# HydraBus_1_0_Rev1_3.net
KiCad netlist of a schematic drawn in EAGLE
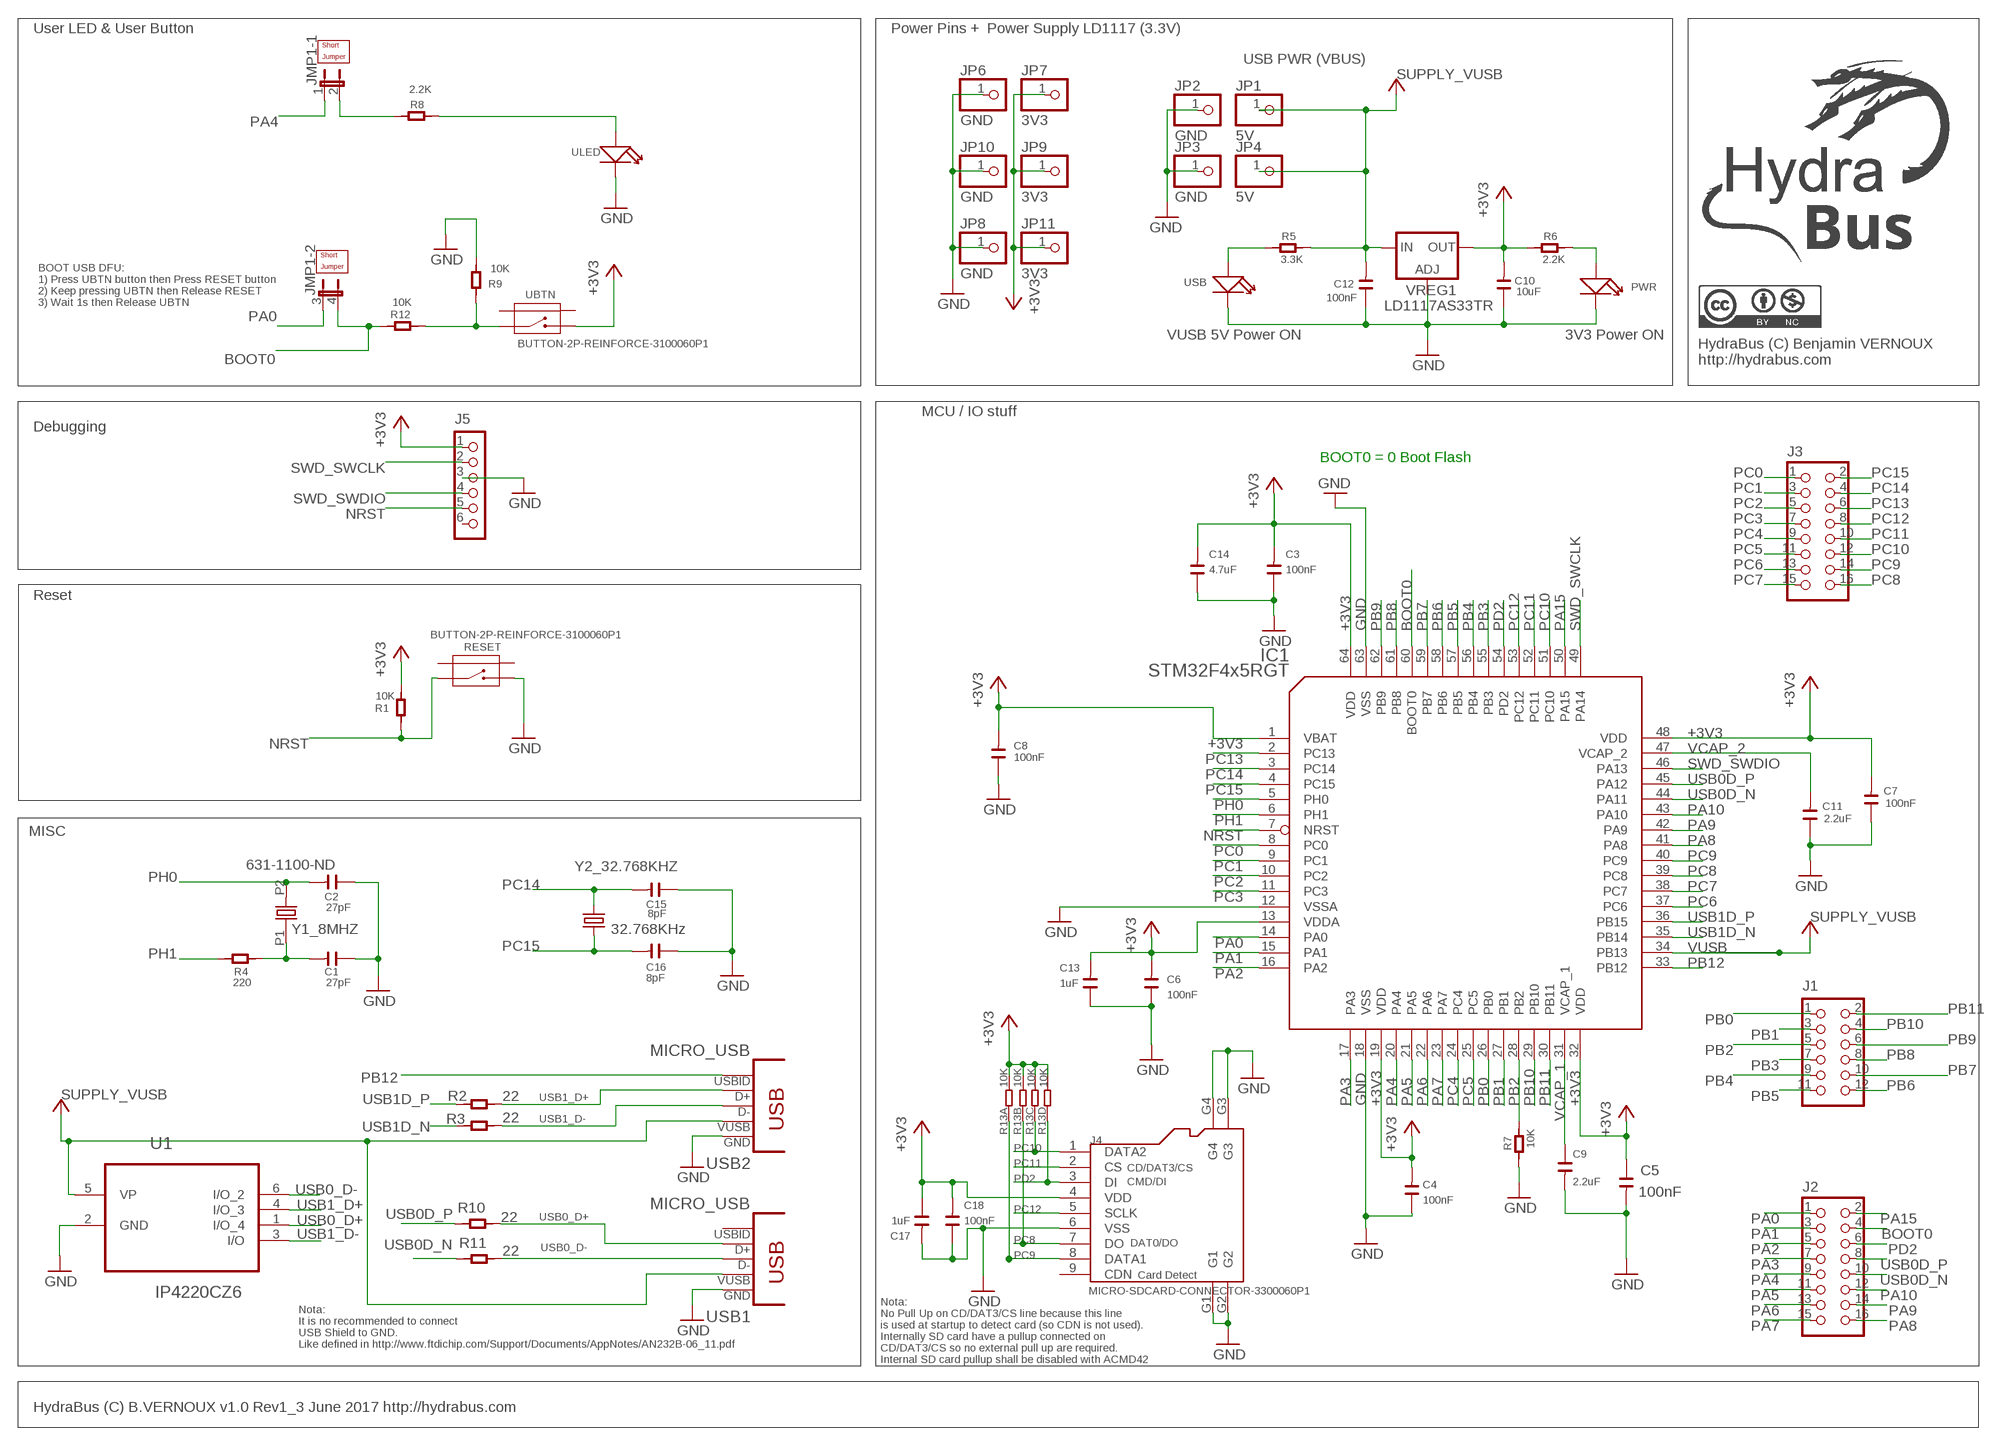
[diagram p0: schematic, sheet 1]

(export (version "E")
  (design (tool "Eeschema 10.0.6"))
  (components
    (comp (ref "C1")
      (value "27pF")
      (footprint "eagle-import:C0603")
      (libsource (lib "eagle-import") (part "C-0603"))
    )
    (comp (ref "C2")
      (value "27pF")
      (footprint "eagle-import:C0603")
      (libsource (lib "eagle-import") (part "C-0603"))
    )
    (comp (ref "C3")
      (value "100nF")
      (footprint "eagle-import:C0603")
      (libsource (lib "eagle-import") (part "C-0603"))
    )
    (comp (ref "C4")
      (value "100nF")
      (footprint "eagle-import:C0603")
      (libsource (lib "eagle-import") (part "C-0603"))
    )
    (comp (ref "C5")
      (value "100nF")
      (footprint "eagle-import:C0603")
      (libsource (lib "eagle-import") (part "C-0603"))
    )
    (comp (ref "C6")
      (value "100nF")
      (footprint "eagle-import:C0603")
      (libsource (lib "eagle-import") (part "C-0603"))
    )
    (comp (ref "C7")
      (value "100nF")
      (footprint "eagle-import:C0603")
      (libsource (lib "eagle-import") (part "C-0603"))
    )
    (comp (ref "C8")
      (value "100nF")
      (footprint "eagle-import:C0603")
      (libsource (lib "eagle-import") (part "C-0603"))
    )
    (comp (ref "C9")
      (value "2.2uF")
      (footprint "eagle-import:C0603")
      (libsource (lib "eagle-import") (part "C-0603"))
    )
    (comp (ref "C10")
      (value "10uF")
      (footprint "eagle-import:C0805")
      (libsource (lib "eagle-import") (part "C-0805"))
    )
    (comp (ref "C11")
      (value "2.2uF")
      (footprint "eagle-import:C0603")
      (libsource (lib "eagle-import") (part "C-0603"))
    )
    (comp (ref "C12")
      (value "100nF")
      (footprint "eagle-import:C0603")
      (libsource (lib "eagle-import") (part "C-0603"))
    )
    (comp (ref "C13")
      (value "1uF")
      (footprint "eagle-import:C0603")
      (libsource (lib "eagle-import") (part "C-0603"))
    )
    (comp (ref "C14")
      (value "4.7uF")
      (footprint "eagle-import:C0603")
      (libsource (lib "eagle-import") (part "C-0603"))
    )
    (comp (ref "C15")
      (value "8pF")
      (footprint "eagle-import:C0603")
      (libsource (lib "eagle-import") (part "C-0603"))
    )
    (comp (ref "C16")
      (value "8pF")
      (footprint "eagle-import:C0603")
      (libsource (lib "eagle-import") (part "C-0603"))
    )
    (comp (ref "C17")
      (value "1uF")
      (footprint "eagle-import:C0603")
      (libsource (lib "eagle-import") (part "C-0603"))
    )
    (comp (ref "C18")
      (value "100nF")
      (footprint "eagle-import:C0603")
      (libsource (lib "eagle-import") (part "C-0603"))
    )
    (comp (ref "IC1")
      (value "STM32F4x5RGT")
      (footprint "eagle-import:LQFP64")
      (libsource (lib "eagle-import") (part "STM32F405RTG"))
    )
    (comp (ref "J1")
      (value "CON_HEADER_2X06")
      (footprint "eagle-import:M2X6")
      (libsource (lib "eagle-import") (part "CON_HEADER_2X06"))
    )
    (comp (ref "J2")
      (value "CON_HEADER_2X08")
      (footprint "eagle-import:M2X8")
      (libsource (lib "eagle-import") (part "CON_HEADER_2X08"))
    )
    (comp (ref "J3")
      (value "CON_HEADER_2X08")
      (footprint "eagle-import:M2X8")
      (libsource (lib "eagle-import") (part "CON_HEADER_2X08"))
    )
    (comp (ref "J4")
      (value "MICRO-SDCARD-CONNECTOR-3300060P1")
      (footprint "eagle-import:9P-SMD-W-RING")
      (libsource (lib "eagle-import") (part "MICRO-SDCARD-CONNECTOR-3300060P1"))
    )
    (comp (ref "J5")
      (value "CON_HEADER_1X06-PTH")
      (footprint "eagle-import:M1X6")
      (libsource (lib "eagle-import") (part "CON_HEADER_1X06-PTH"))
    )
    (comp (ref "JMP1")
      (value "JP2QE")
      (footprint "eagle-import:JP2Q")
      (libsource (lib "eagle-import") (part "JP2QE"))
    )
    (comp (ref "JMP_UBTN")
      (value "SHORT-JUMPER-2P-3460440P1")
      (footprint "eagle-import:2P-2.54")
      (libsource (lib "eagle-import") (part "SHORT-JUMPER-2P-3460440P1"))
    )
    (comp (ref "JMP_ULED")
      (value "SHORT-JUMPER-2P-3460440P1")
      (footprint "eagle-import:2P-2.54")
      (libsource (lib "eagle-import") (part "SHORT-JUMPER-2P-3460440P1"))
    )
    (comp (ref "JP1")
      (value "5V")
      (footprint "eagle-import:1X01")
      (libsource (lib "eagle-import") (part "PINHD-1X1"))
    )
    (comp (ref "JP2")
      (value "GND")
      (footprint "eagle-import:1X01")
      (libsource (lib "eagle-import") (part "PINHD-1X1"))
    )
    (comp (ref "JP3")
      (value "GND")
      (footprint "eagle-import:1X01")
      (libsource (lib "eagle-import") (part "PINHD-1X1"))
    )
    (comp (ref "JP4")
      (value "5V")
      (footprint "eagle-import:1X01")
      (libsource (lib "eagle-import") (part "PINHD-1X1"))
    )
    (comp (ref "JP6")
      (value "GND")
      (footprint "eagle-import:1X01")
      (libsource (lib "eagle-import") (part "PINHD-1X1"))
    )
    (comp (ref "JP7")
      (value "3V3")
      (footprint "eagle-import:1X01")
      (libsource (lib "eagle-import") (part "PINHD-1X1"))
    )
    (comp (ref "JP8")
      (value "GND")
      (footprint "eagle-import:1X01")
      (libsource (lib "eagle-import") (part "PINHD-1X1"))
    )
    (comp (ref "JP9")
      (value "3V3")
      (footprint "eagle-import:1X01")
      (libsource (lib "eagle-import") (part "PINHD-1X1"))
    )
    (comp (ref "JP10")
      (value "GND")
      (footprint "eagle-import:1X01")
      (libsource (lib "eagle-import") (part "PINHD-1X1"))
    )
    (comp (ref "JP11")
      (value "3V3")
      (footprint "eagle-import:1X01")
      (libsource (lib "eagle-import") (part "PINHD-1X1"))
    )
    (comp (ref "PWR")
      (value "LED")
      (footprint "eagle-import:LED0603")
      (libsource (lib "eagle-import") (part "LED"))
    )
    (comp (ref "R1")
      (value "10K")
      (footprint "eagle-import:R0603")
      (libsource (lib "eagle-import") (part "R-0603"))
    )
    (comp (ref "R2")
      (value "22")
      (footprint "eagle-import:R0603")
      (libsource (lib "eagle-import") (part "R-0603"))
    )
    (comp (ref "R3")
      (value "22")
      (footprint "eagle-import:R0603")
      (libsource (lib "eagle-import") (part "R-0603"))
    )
    (comp (ref "R4")
      (value "220")
      (footprint "eagle-import:R0603")
      (libsource (lib "eagle-import") (part "R-0603"))
    )
    (comp (ref "R5")
      (value "3.3K")
      (footprint "eagle-import:R0603")
      (libsource (lib "eagle-import") (part "R-0603"))
    )
    (comp (ref "R6")
      (value "2.2K")
      (footprint "eagle-import:R0603")
      (libsource (lib "eagle-import") (part "R-0603"))
    )
    (comp (ref "R7")
      (value "10K")
      (footprint "eagle-import:R0603")
      (libsource (lib "eagle-import") (part "R-0603"))
    )
    (comp (ref "R8")
      (value "2.2K")
      (footprint "eagle-import:R0603")
      (libsource (lib "eagle-import") (part "R-0603"))
    )
    (comp (ref "R9")
      (value "10K")
      (footprint "eagle-import:R0603")
      (libsource (lib "eagle-import") (part "R-0603"))
    )
    (comp (ref "R10")
      (value "22")
      (footprint "eagle-import:R0603")
      (libsource (lib "eagle-import") (part "R-0603"))
    )
    (comp (ref "R11")
      (value "22")
      (footprint "eagle-import:R0603")
      (libsource (lib "eagle-import") (part "R-0603"))
    )
    (comp (ref "R12")
      (value "10K")
      (footprint "eagle-import:R0603")
      (libsource (lib "eagle-import") (part "R-0603"))
    )
    (comp (ref "R13")
      (value "10K")
      (footprint "eagle-import:R1206-8")
      (fields (field (name "OPL") "0040070P1 SMD RES ARRAY 10K OHM 4 RES 1206"))
      (libsource (lib "eagle-import") (part "R-4R"))
    )
    (comp (ref "RESET")
      (value "BUTTON-2P-REINFORCE-3100060P1")
      (footprint "eagle-import:4P-SMD-7.0X3.5X3.5H-90D")
      (libsource (lib "eagle-import") (part "BUTTON-2P-REINFORCE-3100060P1"))
    )
    (comp (ref "U1")
      (value "IP4220CZ6")
      (footprint "eagle-import:SOT95P275X110-6N")
      (libsource (lib "eagle-import") (part "IP4220CZ6"))
    )
    (comp (ref "UBTN")
      (value "BUTTON-2P-REINFORCE-3100060P1")
      (footprint "eagle-import:4P-SMD-7.0X3.5X3.5H-90D")
      (libsource (lib "eagle-import") (part "BUTTON-2P-REINFORCE-3100060P1"))
    )
    (comp (ref "ULED")
      (value "LED")
      (footprint "eagle-import:LED0603")
      (libsource (lib "eagle-import") (part "LED"))
    )
    (comp (ref "USB")
      (value "LED")
      (footprint "eagle-import:LED0603")
      (libsource (lib "eagle-import") (part "LED"))
    )
    (comp (ref "USB1")
      (value "MICRO_USB")
      (footprint "eagle-import:MICRO_USB5+6P_SMD_0_65")
      (libsource (lib "eagle-import") (part "MICRO_USB"))
    )
    (comp (ref "USB2")
      (value "MICRO_USB")
      (footprint "eagle-import:MICRO_USB5+6P_SMD_0_65")
      (libsource (lib "eagle-import") (part "MICRO_USB"))
    )
    (comp (ref "VREG1")
      (value "LD1117AS33TR")
      (footprint "eagle-import:SOT223")
      (libsource (lib "eagle-import") (part "LD117A?S33TR"))
    )
    (comp (ref "Y1_8MHZ")
      (value "631-1100-ND")
      (footprint "eagle-import:HC-49U-PTH")
      (libsource (lib "eagle-import") (part "OSC-XTAL-HC-49U-PTH"))
    )
    (comp (ref "Y2_32.768KHZ")
      (value "32.768KHz")
      (footprint "eagle-import:TC38H")
      (libsource (lib "eagle-import") (part "CRYSTALTC38H"))
    )
  )
  (nets
    (net (code "1") (name "+3V3") (class "Default")
      (node (ref "C10") (pin "1") (pinfunction "1_1") (pintype "bidirectional"))
      (node (ref "C13") (pin "1") (pinfunction "1_1") (pintype "bidirectional"))
      (node (ref "C14") (pin "1") (pinfunction "1_1") (pintype "bidirectional"))
      (node (ref "C17") (pin "2") (pinfunction "2_2") (pintype "bidirectional"))
      (node (ref "C18") (pin "1") (pinfunction "1_1") (pintype "bidirectional"))
      (node (ref "C3") (pin "1") (pinfunction "1_1") (pintype "bidirectional"))
      (node (ref "C4") (pin "1") (pinfunction "1_1") (pintype "bidirectional"))
      (node (ref "C5") (pin "2") (pinfunction "2_2") (pintype "bidirectional"))
      (node (ref "C6") (pin "1") (pinfunction "1_1") (pintype "bidirectional"))
      (node (ref "C7") (pin "1") (pinfunction "1_1") (pintype "bidirectional"))
      (node (ref "C8") (pin "1") (pinfunction "1_1") (pintype "bidirectional"))
      (node (ref "IC1") (pin "1") (pinfunction "VBAT_1") (pintype "power_in"))
      (node (ref "IC1") (pin "13") (pinfunction "VDDA_13") (pintype "power_in"))
      (node (ref "IC1") (pin "19") (pinfunction "VDD_19") (pintype "power_in"))
      (node (ref "IC1") (pin "32") (pinfunction "VDD_32") (pintype "power_in"))
      (node (ref "IC1") (pin "48") (pinfunction "VDD_48") (pintype "power_in"))
      (node (ref "IC1") (pin "64") (pinfunction "VDD_64") (pintype "power_in"))
      (node (ref "J4") (pin "4") (pinfunction "VDD_4") (pintype "bidirectional"))
      (node (ref "J5") (pin "1") (pinfunction "1_1") (pintype "bidirectional"))
      (node (ref "JP11") (pin "1") (pinfunction "1_1") (pintype "passive"))
      (node (ref "JP7") (pin "1") (pinfunction "1_1") (pintype "passive"))
      (node (ref "JP9") (pin "1") (pinfunction "1_1") (pintype "passive"))
      (node (ref "R1") (pin "2") (pinfunction "2_2") (pintype "bidirectional"))
      (node (ref "R13") (pin "5") (pinfunction "2_5") (pintype "passive"))
      (node (ref "R13") (pin "6") (pinfunction "2_6") (pintype "passive"))
      (node (ref "R13") (pin "7") (pinfunction "2_7") (pintype "passive"))
      (node (ref "R13") (pin "8") (pinfunction "2_8") (pintype "passive"))
      (node (ref "R6") (pin "2") (pinfunction "2_2") (pintype "bidirectional"))
      (node (ref "UBTN") (pin "2") (pinfunction "2_2") (pintype "bidirectional"))
      (node (ref "VREG1") (pin "4") (pinfunction "OUT_4") (pintype "passive"))
    )
    (net (code "2") (name "/BOOT0") (class "Default")
      (node (ref "IC1") (pin "60") (pinfunction "BOOT0_60") (pintype "bidirectional"))
      (node (ref "J2") (pin "4") (pinfunction "4_4") (pintype "passive"))
      (node (ref "JMP1") (pin "4") (pinfunction "2_4") (pintype "passive"))
      (node (ref "R12") (pin "2") (pinfunction "2_2") (pintype "bidirectional"))
    )
    (net (code "3") (name "/NRST") (class "Default")
      (node (ref "IC1") (pin "7") (pinfunction "NRST_7") (pintype "input"))
      (node (ref "J5") (pin "5") (pinfunction "5_5") (pintype "passive"))
      (node (ref "R1") (pin "1") (pinfunction "1_1") (pintype "bidirectional"))
      (node (ref "RESET") (pin "1") (pinfunction "1_1") (pintype "bidirectional"))
    )
    (net (code "4") (name "/PA0") (class "Default")
      (node (ref "IC1") (pin "14") (pinfunction "PA0_14") (pintype "bidirectional"))
      (node (ref "J2") (pin "1") (pinfunction "1_1") (pintype "passive"))
      (node (ref "JMP1") (pin "3") (pinfunction "1_3") (pintype "passive"))
    )
    (net (code "5") (name "/PA1") (class "Default")
      (node (ref "IC1") (pin "15") (pinfunction "PA1_15") (pintype "bidirectional"))
      (node (ref "J2") (pin "3") (pinfunction "3_3") (pintype "passive"))
    )
    (net (code "6") (name "/PA2") (class "Default")
      (node (ref "IC1") (pin "16") (pinfunction "PA2_16") (pintype "bidirectional"))
      (node (ref "J2") (pin "5") (pinfunction "5_5") (pintype "passive"))
    )
    (net (code "7") (name "/PA3") (class "Default")
      (node (ref "IC1") (pin "17") (pinfunction "PA3_17") (pintype "bidirectional"))
      (node (ref "J2") (pin "7") (pinfunction "7_7") (pintype "passive"))
    )
    (net (code "8") (name "/PA4") (class "Default")
      (node (ref "IC1") (pin "20") (pinfunction "PA4_20") (pintype "bidirectional"))
      (node (ref "J2") (pin "9") (pinfunction "9_9") (pintype "passive"))
      (node (ref "JMP1") (pin "1") (pinfunction "1_1") (pintype "passive"))
    )
    (net (code "9") (name "/PA5") (class "Default")
      (node (ref "IC1") (pin "21") (pinfunction "PA5_21") (pintype "bidirectional"))
      (node (ref "J2") (pin "11") (pinfunction "11_11") (pintype "passive"))
    )
    (net (code "10") (name "/PA6") (class "Default")
      (node (ref "IC1") (pin "22") (pinfunction "PA6_22") (pintype "bidirectional"))
      (node (ref "J2") (pin "13") (pinfunction "13_13") (pintype "passive"))
    )
    (net (code "11") (name "/PA7") (class "Default")
      (node (ref "IC1") (pin "23") (pinfunction "PA7_23") (pintype "bidirectional"))
      (node (ref "J2") (pin "15") (pinfunction "15_15") (pintype "passive"))
    )
    (net (code "12") (name "/PA8") (class "Default")
      (node (ref "IC1") (pin "41") (pinfunction "PA8_41") (pintype "bidirectional"))
      (node (ref "J2") (pin "16") (pinfunction "16_16") (pintype "passive"))
    )
    (net (code "13") (name "/PA9") (class "Default")
      (node (ref "IC1") (pin "42") (pinfunction "PA9_42") (pintype "bidirectional"))
      (node (ref "J2") (pin "14") (pinfunction "14_14") (pintype "passive"))
    )
    (net (code "14") (name "/PA10") (class "Default")
      (node (ref "IC1") (pin "43") (pinfunction "PA10_43") (pintype "bidirectional"))
      (node (ref "J2") (pin "12") (pinfunction "12_12") (pintype "passive"))
    )
    (net (code "15") (name "/PA15") (class "Default")
      (node (ref "IC1") (pin "50") (pinfunction "PA15_50") (pintype "bidirectional"))
      (node (ref "J2") (pin "2") (pinfunction "2_2") (pintype "passive"))
    )
    (net (code "16") (name "/PB0") (class "Default")
      (node (ref "IC1") (pin "26") (pinfunction "PB0_26") (pintype "bidirectional"))
      (node (ref "J1") (pin "1") (pinfunction "1_1") (pintype "passive"))
    )
    (net (code "17") (name "/PB1") (class "Default")
      (node (ref "IC1") (pin "27") (pinfunction "PB1_27") (pintype "bidirectional"))
      (node (ref "J1") (pin "3") (pinfunction "3_3") (pintype "passive"))
    )
    (net (code "18") (name "/PB2") (class "Default")
      (node (ref "IC1") (pin "28") (pinfunction "PB2_28") (pintype "bidirectional"))
      (node (ref "J1") (pin "5") (pinfunction "5_5") (pintype "passive"))
      (node (ref "R7") (pin "1") (pinfunction "1_1") (pintype "bidirectional"))
    )
    (net (code "19") (name "/PB3") (class "Default")
      (node (ref "IC1") (pin "55") (pinfunction "PB3_55") (pintype "bidirectional"))
      (node (ref "J1") (pin "7") (pinfunction "7_7") (pintype "passive"))
    )
    (net (code "20") (name "/PB4") (class "Default")
      (node (ref "IC1") (pin "56") (pinfunction "PB4_56") (pintype "bidirectional"))
      (node (ref "J1") (pin "9") (pinfunction "9_9") (pintype "passive"))
    )
    (net (code "21") (name "/PB5") (class "Default")
      (node (ref "IC1") (pin "57") (pinfunction "PB5_57") (pintype "bidirectional"))
      (node (ref "J1") (pin "11") (pinfunction "11_11") (pintype "passive"))
    )
    (net (code "22") (name "/PB6") (class "Default")
      (node (ref "IC1") (pin "58") (pinfunction "PB6_58") (pintype "bidirectional"))
      (node (ref "J1") (pin "12") (pinfunction "12_12") (pintype "passive"))
    )
    (net (code "23") (name "/PB7") (class "Default")
      (node (ref "IC1") (pin "59") (pinfunction "PB7_59") (pintype "bidirectional"))
      (node (ref "J1") (pin "10") (pinfunction "10_10") (pintype "passive"))
    )
    (net (code "24") (name "/PB8") (class "Default")
      (node (ref "IC1") (pin "61") (pinfunction "PB8_61") (pintype "bidirectional"))
      (node (ref "J1") (pin "8") (pinfunction "8_8") (pintype "passive"))
    )
    (net (code "25") (name "/PB9") (class "Default")
      (node (ref "IC1") (pin "62") (pinfunction "PB9_62") (pintype "bidirectional"))
      (node (ref "J1") (pin "6") (pinfunction "6_6") (pintype "passive"))
    )
    (net (code "26") (name "/PB10") (class "Default")
      (node (ref "IC1") (pin "29") (pinfunction "PB10_29") (pintype "bidirectional"))
      (node (ref "J1") (pin "4") (pinfunction "4_4") (pintype "passive"))
    )
    (net (code "27") (name "/PB11") (class "Default")
      (node (ref "IC1") (pin "30") (pinfunction "PB11_30") (pintype "bidirectional"))
      (node (ref "J1") (pin "2") (pinfunction "2_2") (pintype "passive"))
    )
    (net (code "28") (name "/PB12") (class "Default")
      (node (ref "IC1") (pin "33") (pinfunction "PB12_33") (pintype "bidirectional"))
      (node (ref "USB2") (pin "4") (pinfunction "USBID_4") (pintype "bidirectional"))
    )
    (net (code "29") (name "/PC0") (class "Default")
      (node (ref "IC1") (pin "8") (pinfunction "PC0_8") (pintype "bidirectional"))
      (node (ref "J3") (pin "1") (pinfunction "1_1") (pintype "passive"))
    )
    (net (code "30") (name "/PC1") (class "Default")
      (node (ref "IC1") (pin "9") (pinfunction "PC1_9") (pintype "bidirectional"))
      (node (ref "J3") (pin "3") (pinfunction "3_3") (pintype "passive"))
    )
    (net (code "31") (name "/PC2") (class "Default")
      (node (ref "IC1") (pin "10") (pinfunction "PC2_10") (pintype "bidirectional"))
      (node (ref "J3") (pin "5") (pinfunction "5_5") (pintype "passive"))
    )
    (net (code "32") (name "/PC3") (class "Default")
      (node (ref "IC1") (pin "11") (pinfunction "PC3_11") (pintype "bidirectional"))
      (node (ref "J3") (pin "7") (pinfunction "7_7") (pintype "passive"))
    )
    (net (code "33") (name "/PC4") (class "Default")
      (node (ref "IC1") (pin "24") (pinfunction "PC4_24") (pintype "bidirectional"))
      (node (ref "J3") (pin "9") (pinfunction "9_9") (pintype "passive"))
    )
    (net (code "34") (name "/PC5") (class "Default")
      (node (ref "IC1") (pin "25") (pinfunction "PC5_25") (pintype "bidirectional"))
      (node (ref "J3") (pin "11") (pinfunction "11_11") (pintype "passive"))
    )
    (net (code "35") (name "/PC6") (class "Default")
      (node (ref "IC1") (pin "37") (pinfunction "PC6_37") (pintype "bidirectional"))
      (node (ref "J3") (pin "13") (pinfunction "13_13") (pintype "passive"))
    )
    (net (code "36") (name "/PC7") (class "Default")
      (node (ref "IC1") (pin "38") (pinfunction "PC7_38") (pintype "bidirectional"))
      (node (ref "J3") (pin "15") (pinfunction "15_15") (pintype "passive"))
    )
    (net (code "37") (name "/PC8") (class "Default")
      (node (ref "IC1") (pin "39") (pinfunction "PC8_39") (pintype "bidirectional"))
      (node (ref "J3") (pin "16") (pinfunction "16_16") (pintype "passive"))
      (node (ref "J4") (pin "7") (pinfunction "DO_7") (pintype "bidirectional"))
      (node (ref "R13") (pin "2") (pinfunction "1_2") (pintype "passive"))
    )
    (net (code "38") (name "/PC9") (class "Default")
      (node (ref "IC1") (pin "40") (pinfunction "PC9_40") (pintype "bidirectional"))
      (node (ref "J3") (pin "14") (pinfunction "14_14") (pintype "passive"))
      (node (ref "J4") (pin "8") (pinfunction "DATA1_8") (pintype "bidirectional"))
      (node (ref "R13") (pin "1") (pinfunction "1_1") (pintype "passive"))
    )
    (net (code "39") (name "/PC10") (class "Default")
      (node (ref "IC1") (pin "51") (pinfunction "PC10_51") (pintype "bidirectional"))
      (node (ref "J3") (pin "12") (pinfunction "12_12") (pintype "passive"))
      (node (ref "J4") (pin "1") (pinfunction "DATA2_1") (pintype "bidirectional"))
      (node (ref "R13") (pin "3") (pinfunction "1_3") (pintype "passive"))
    )
    (net (code "40") (name "/PC11") (class "Default")
      (node (ref "IC1") (pin "52") (pinfunction "PC11_52") (pintype "bidirectional"))
      (node (ref "J3") (pin "10") (pinfunction "10_10") (pintype "passive"))
      (node (ref "J4") (pin "2") (pinfunction "CS_2") (pintype "bidirectional"))
    )
    (net (code "41") (name "/PC12") (class "Default")
      (node (ref "IC1") (pin "53") (pinfunction "PC12_53") (pintype "bidirectional"))
      (node (ref "J3") (pin "8") (pinfunction "8_8") (pintype "passive"))
      (node (ref "J4") (pin "5") (pinfunction "SCLK_5") (pintype "bidirectional"))
    )
    (net (code "42") (name "/PC13") (class "Default")
      (node (ref "IC1") (pin "2") (pinfunction "PC13_2") (pintype "bidirectional"))
      (node (ref "J3") (pin "6") (pinfunction "6_6") (pintype "passive"))
    )
    (net (code "43") (name "/PC14") (class "Default")
      (node (ref "C15") (pin "1") (pinfunction "1_1") (pintype "bidirectional"))
      (node (ref "IC1") (pin "3") (pinfunction "PC14_3") (pintype "bidirectional"))
      (node (ref "J3") (pin "4") (pinfunction "4_4") (pintype "passive"))
      (node (ref "Y2_32.768KHZ") (pin "2") (pinfunction "2_2") (pintype "passive"))
    )
    (net (code "44") (name "/PC15") (class "Default")
      (node (ref "C16") (pin "1") (pinfunction "1_1") (pintype "bidirectional"))
      (node (ref "IC1") (pin "4") (pinfunction "PC15_4") (pintype "bidirectional"))
      (node (ref "J3") (pin "2") (pinfunction "2_2") (pintype "passive"))
      (node (ref "Y2_32.768KHZ") (pin "1") (pinfunction "1_1") (pintype "passive"))
    )
    (net (code "45") (name "/PD2") (class "Default")
      (node (ref "IC1") (pin "54") (pinfunction "PD2_54") (pintype "bidirectional"))
      (node (ref "J2") (pin "6") (pinfunction "6_6") (pintype "passive"))
      (node (ref "J4") (pin "3") (pinfunction "DI_3") (pintype "bidirectional"))
      (node (ref "R13") (pin "4") (pinfunction "1_4") (pintype "passive"))
    )
    (net (code "46") (name "/PH0") (class "Default")
      (node (ref "C2") (pin "1") (pinfunction "1_1") (pintype "bidirectional"))
      (node (ref "IC1") (pin "5") (pinfunction "PH0_5") (pintype "bidirectional"))
      (node (ref "Y1_8MHZ") (pin "P2") (pinfunction "2_P2") (pintype "passive"))
    )
    (net (code "47") (name "/PH1") (class "Default")
      (node (ref "IC1") (pin "6") (pinfunction "PH1_6") (pintype "bidirectional"))
      (node (ref "R4") (pin "2") (pinfunction "2_2") (pintype "bidirectional"))
    )
    (net (code "48") (name "/SWD_SWCLK") (class "Default")
      (node (ref "IC1") (pin "49") (pinfunction "PA14_49") (pintype "bidirectional"))
      (node (ref "J5") (pin "2") (pinfunction "2_2") (pintype "bidirectional"))
    )
    (net (code "49") (name "/SWD_SWDIO") (class "Default")
      (node (ref "IC1") (pin "46") (pinfunction "PA13_46") (pintype "bidirectional"))
      (node (ref "J5") (pin "4") (pinfunction "4_4") (pintype "passive"))
    )
    (net (code "50") (name "/USB0D_N") (class "Default")
      (node (ref "IC1") (pin "44") (pinfunction "PA11_44") (pintype "bidirectional"))
      (node (ref "J2") (pin "10") (pinfunction "10_10") (pintype "passive"))
      (node (ref "R11") (pin "2") (pinfunction "2_2") (pintype "bidirectional"))
    )
    (net (code "51") (name "/USB0D_P") (class "Default")
      (node (ref "IC1") (pin "45") (pinfunction "PA12_45") (pintype "bidirectional"))
      (node (ref "J2") (pin "8") (pinfunction "8_8") (pintype "passive"))
      (node (ref "R10") (pin "2") (pinfunction "2_2") (pintype "bidirectional"))
    )
    (net (code "52") (name "/USB0_D+") (class "Default")
      (node (ref "R10") (pin "1") (pinfunction "1_1") (pintype "bidirectional"))
      (node (ref "U1") (pin "1") (pinfunction "I/O_4_1") (pintype "bidirectional"))
      (node (ref "USB1") (pin "3") (pinfunction "D+_3") (pintype "bidirectional"))
    )
    (net (code "53") (name "/USB0_D-") (class "Default")
      (node (ref "R11") (pin "1") (pinfunction "1_1") (pintype "bidirectional"))
      (node (ref "U1") (pin "6") (pinfunction "I/O_2_6") (pintype "bidirectional"))
      (node (ref "USB1") (pin "2") (pinfunction "D-_2") (pintype "bidirectional"))
    )
    (net (code "54") (name "/USB1D_N") (class "Default")
      (node (ref "IC1") (pin "35") (pinfunction "PB14_35") (pintype "bidirectional"))
      (node (ref "R3") (pin "2") (pinfunction "2_2") (pintype "bidirectional"))
    )
    (net (code "55") (name "/USB1D_P") (class "Default")
      (node (ref "IC1") (pin "36") (pinfunction "PB15_36") (pintype "bidirectional"))
      (node (ref "R2") (pin "2") (pinfunction "2_2") (pintype "bidirectional"))
    )
    (net (code "56") (name "/USB1_D+") (class "Default")
      (node (ref "R2") (pin "1") (pinfunction "1_1") (pintype "bidirectional"))
      (node (ref "U1") (pin "4") (pinfunction "I/O_3_4") (pintype "bidirectional"))
      (node (ref "USB2") (pin "3") (pinfunction "D+_3") (pintype "bidirectional"))
    )
    (net (code "57") (name "/USB1_D-") (class "Default")
      (node (ref "R3") (pin "1") (pinfunction "1_1") (pintype "bidirectional"))
      (node (ref "U1") (pin "3") (pinfunction "I/O_3") (pintype "bidirectional"))
      (node (ref "USB2") (pin "2") (pinfunction "D-_2") (pintype "bidirectional"))
    )
    (net (code "58") (name "/VCAP_1") (class "Default")
      (node (ref "C9") (pin "2") (pinfunction "2_2") (pintype "bidirectional"))
      (node (ref "IC1") (pin "31") (pinfunction "VCAP_1_31") (pintype "passive"))
    )
    (net (code "59") (name "/VCAP_2") (class "Default")
      (node (ref "C11") (pin "1") (pinfunction "1_1") (pintype "bidirectional"))
      (node (ref "IC1") (pin "47") (pinfunction "VCAP_2_47") (pintype "passive"))
    )
    (net (code "60") (name "GND") (class "Default")
      (node (ref "C1") (pin "2") (pinfunction "2_2") (pintype "bidirectional"))
      (node (ref "C10") (pin "2") (pinfunction "2_2") (pintype "bidirectional"))
      (node (ref "C11") (pin "2") (pinfunction "2_2") (pintype "bidirectional"))
      (node (ref "C12") (pin "2") (pinfunction "2_2") (pintype "bidirectional"))
      (node (ref "C13") (pin "2") (pinfunction "2_2") (pintype "bidirectional"))
      (node (ref "C14") (pin "2") (pinfunction "2_2") (pintype "bidirectional"))
      (node (ref "C15") (pin "2") (pinfunction "2_2") (pintype "bidirectional"))
      (node (ref "C16") (pin "2") (pinfunction "2_2") (pintype "bidirectional"))
      (node (ref "C17") (pin "1") (pinfunction "1_1") (pintype "bidirectional"))
      (node (ref "C18") (pin "2") (pinfunction "2_2") (pintype "bidirectional"))
      (node (ref "C2") (pin "2") (pinfunction "2_2") (pintype "bidirectional"))
      (node (ref "C3") (pin "2") (pinfunction "2_2") (pintype "bidirectional"))
      (node (ref "C4") (pin "2") (pinfunction "2_2") (pintype "bidirectional"))
      (node (ref "C5") (pin "1") (pinfunction "1_1") (pintype "bidirectional"))
      (node (ref "C6") (pin "2") (pinfunction "2_2") (pintype "bidirectional"))
      (node (ref "C7") (pin "2") (pinfunction "2_2") (pintype "bidirectional"))
      (node (ref "C8") (pin "2") (pinfunction "2_2") (pintype "bidirectional"))
      (node (ref "C9") (pin "1") (pinfunction "1_1") (pintype "bidirectional"))
      (node (ref "IC1") (pin "12") (pinfunction "VSSA_12") (pintype "power_in"))
      (node (ref "IC1") (pin "18") (pinfunction "VSS_18") (pintype "power_in"))
      (node (ref "IC1") (pin "63") (pinfunction "VSS_63") (pintype "power_in"))
      (node (ref "J4") (pin "6") (pinfunction "VSS_6") (pintype "bidirectional"))
      (node (ref "J4") (pin "G1") (pinfunction "G1_G1") (pintype "bidirectional"))
      (node (ref "J4") (pin "G2") (pinfunction "G2_G2") (pintype "bidirectional"))
      (node (ref "J4") (pin "G3") (pinfunction "G3_G3") (pintype "bidirectional"))
      (node (ref "J4") (pin "G4") (pinfunction "G4_G4") (pintype "bidirectional"))
      (node (ref "J5") (pin "3") (pinfunction "3_3") (pintype "passive"))
      (node (ref "JP10") (pin "1") (pinfunction "1_1") (pintype "passive"))
      (node (ref "JP2") (pin "1") (pinfunction "1_1") (pintype "passive"))
      (node (ref "JP3") (pin "1") (pinfunction "1_1") (pintype "passive"))
      (node (ref "JP6") (pin "1") (pinfunction "1_1") (pintype "passive"))
      (node (ref "JP8") (pin "1") (pinfunction "1_1") (pintype "passive"))
      (node (ref "PWR") (pin "-") (pinfunction "-_-") (pintype "passive"))
      (node (ref "R7") (pin "2") (pinfunction "2_2") (pintype "bidirectional"))
      (node (ref "R9") (pin "2") (pinfunction "2_2") (pintype "bidirectional"))
      (node (ref "RESET") (pin "2") (pinfunction "2_2") (pintype "bidirectional"))
      (node (ref "U1") (pin "2") (pinfunction "GND_2") (pintype "passive"))
      (node (ref "ULED") (pin "-") (pinfunction "-_-") (pintype "passive"))
      (node (ref "USB") (pin "-") (pinfunction "-_-") (pintype "passive"))
      (node (ref "USB1") (pin "5") (pinfunction "GND_5") (pintype "bidirectional"))
      (node (ref "USB2") (pin "5") (pinfunction "GND_5") (pintype "bidirectional"))
      (node (ref "VREG1") (pin "1") (pinfunction "ADJ_1") (pintype "input"))
    )
    (net (code "61") (name "Net-(JMP1-Pad2)") (class "Default")
      (node (ref "JMP1") (pin "2") (pinfunction "2_2") (pintype "passive"))
      (node (ref "R8") (pin "2") (pinfunction "2_2") (pintype "bidirectional"))
    )
    (net (code "62") (name "Net-(PWR-Pad+)") (class "Default")
      (node (ref "PWR") (pin "+") (pinfunction "+_+") (pintype "passive"))
      (node (ref "R6") (pin "1") (pinfunction "1_1") (pintype "bidirectional"))
    )
    (net (code "63") (name "Net-(R5-Pad2)") (class "Default")
      (node (ref "R5") (pin "2") (pinfunction "2_2") (pintype "bidirectional"))
      (node (ref "USB") (pin "+") (pinfunction "+_+") (pintype "passive"))
    )
    (net (code "64") (name "Net-(R8-Pad1)") (class "Default")
      (node (ref "R8") (pin "1") (pinfunction "1_1") (pintype "bidirectional"))
      (node (ref "ULED") (pin "+") (pinfunction "+_+") (pintype "passive"))
    )
    (net (code "65") (name "Net-(R12-Pad1)") (class "Default")
      (node (ref "R12") (pin "1") (pinfunction "1_1") (pintype "bidirectional"))
      (node (ref "R9") (pin "1") (pinfunction "1_1") (pintype "bidirectional"))
      (node (ref "UBTN") (pin "1") (pinfunction "1_1") (pintype "bidirectional"))
    )
    (net (code "66") (name "Net-(Y1_8MHZ-1)") (class "Default")
      (node (ref "C1") (pin "1") (pinfunction "1_1") (pintype "bidirectional"))
      (node (ref "R4") (pin "1") (pinfunction "1_1") (pintype "bidirectional"))
      (node (ref "Y1_8MHZ") (pin "P1") (pinfunction "1_P1") (pintype "passive"))
    )
    (net (code "67") (name "SUPPLY_VUSB") (class "Default")
      (node (ref "C12") (pin "1") (pinfunction "1_1") (pintype "bidirectional"))
      (node (ref "IC1") (pin "34") (pinfunction "PB13_34") (pintype "bidirectional"))
      (node (ref "JP1") (pin "1") (pinfunction "1_1") (pintype "passive"))
      (node (ref "JP4") (pin "1") (pinfunction "1_1") (pintype "passive"))
      (node (ref "R5") (pin "1") (pinfunction "1_1") (pintype "bidirectional"))
      (node (ref "U1") (pin "5") (pinfunction "VP_5") (pintype "power_in"))
      (node (ref "USB1") (pin "1") (pinfunction "VUSB_1") (pintype "bidirectional"))
      (node (ref "USB2") (pin "1") (pinfunction "VUSB_1") (pintype "bidirectional"))
      (node (ref "VREG1") (pin "3") (pinfunction "IN_3") (pintype "input"))
    )
    (net (code "68") (name "unconnected-(J4-CDN-Pad9)") (class "Default")
      (node (ref "J4") (pin "9") (pinfunction "CDN_9") (pintype "bidirectional"))
    )
    (net (code "69") (name "unconnected-(J5-Pad6)") (class "Default")
      (node (ref "J5") (pin "6") (pinfunction "6_6") (pintype "passive"))
    )
    (net (code "70") (name "unconnected-(RESET-PadS1)") (class "Default")
      (node (ref "RESET") (pin "S1") (pinfunction "S1_S1") (pintype "bidirectional"))
    )
    (net (code "71") (name "unconnected-(RESET-PadS2)") (class "Default")
      (node (ref "RESET") (pin "S2") (pinfunction "S2_S2") (pintype "bidirectional"))
    )
    (net (code "72") (name "unconnected-(UBTN-PadS1)") (class "Default")
      (node (ref "UBTN") (pin "S1") (pinfunction "S1_S1") (pintype "bidirectional"))
    )
    (net (code "73") (name "unconnected-(UBTN-PadS2)") (class "Default")
      (node (ref "UBTN") (pin "S2") (pinfunction "S2_S2") (pintype "bidirectional"))
    )
    (net (code "74") (name "unconnected-(USB1-USBID-Pad4)") (class "Default")
      (node (ref "USB1") (pin "4") (pinfunction "USBID_4") (pintype "bidirectional"))
    )
  )
)
